# Pin_Connections.net
KiCad netlist of a schematic drawn in Altium Designer
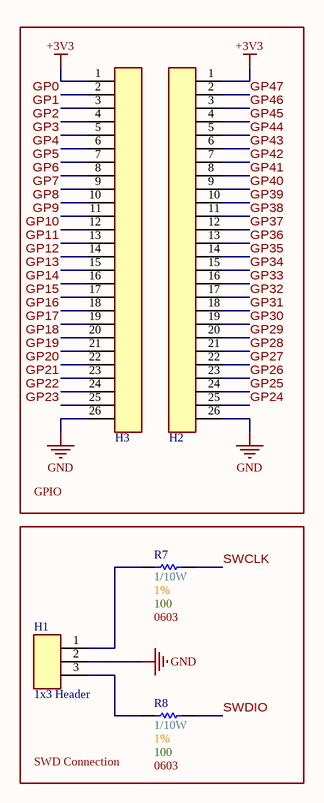
[diagram p0: Pin Connections.SchDoc]

(export (version "E")
  (design (tool "Eeschema 10.0.6"))
  (components
    (comp (ref "H1")
      (value "1x3 Header")
      (footprint "[Header] 1x3 Male")
      (description "2.54mm pitch")
      (libsource (lib "Connectors") (part "[Header] 1x3 Male"))
    )
    (comp (ref "H2")
      (value "1x26 Header")
      (footprint "[Header] 1x26 Male")
      (description "2.54mm pitch")
      (libsource (lib "") (part "[Header] 1x26 Male_1"))
    )
    (comp (ref "H3")
      (value "1x26 Header")
      (footprint "[Header] 1x26 Male")
      (description "2.54mm pitch")
      (libsource (lib "Connectors") (part "[Header] 1x26 Male"))
    )
    (comp (ref "R7")
      (value "[100] SMD 0603 1% 1/10W")
      (footprint "[Res] SMD 0603")
      (description "RC0603FR-07100RL")
      (fields
        (field (name "WATTAGE") "1/10W")
        (field (name "TOLERANCE") "1%")
        (field (name "RESISTANCE") "100")
        (field (name "SIZE PACKAGE") "0603")
      )
      (libsource (lib "Resistors") (part "[100] SMD 0603 1% 1/10W"))
    )
    (comp (ref "R8")
      (value "[100] SMD 0603 1% 1/10W")
      (footprint "[Res] SMD 0603")
      (description "RC0603FR-07100RL")
      (fields
        (field (name "WATTAGE") "1/10W")
        (field (name "TOLERANCE") "1%")
        (field (name "RESISTANCE") "100")
        (field (name "SIZE PACKAGE") "0603")
      )
      (libsource (lib "Resistors") (part "[100] SMD 0603 1% 1/10W"))
    )
  )
  (nets
    (net (code "1") (name "+3V3") (class "Default")
      (node (ref "H2") (pin "1") (pinfunction "1_1") (pintype "passive"))
      (node (ref "H3") (pin "1") (pinfunction "1_1") (pintype "passive"))
    )
    (net (code "2") (name "/GP0") (class "Default")
      (node (ref "H3") (pin "2") (pinfunction "2_2") (pintype "passive"))
    )
    (net (code "3") (name "/GP1") (class "Default")
      (node (ref "H3") (pin "3") (pinfunction "3_3") (pintype "passive"))
    )
    (net (code "4") (name "/GP2") (class "Default")
      (node (ref "H3") (pin "4") (pinfunction "4_4") (pintype "passive"))
    )
    (net (code "5") (name "/GP3") (class "Default")
      (node (ref "H3") (pin "5") (pinfunction "5_5") (pintype "passive"))
    )
    (net (code "6") (name "/GP4") (class "Default")
      (node (ref "H3") (pin "6") (pinfunction "6_6") (pintype "passive"))
    )
    (net (code "7") (name "/GP5") (class "Default")
      (node (ref "H3") (pin "7") (pinfunction "7_7") (pintype "passive"))
    )
    (net (code "8") (name "/GP6") (class "Default")
      (node (ref "H3") (pin "8") (pinfunction "8_8") (pintype "passive"))
    )
    (net (code "9") (name "/GP7") (class "Default")
      (node (ref "H3") (pin "9") (pinfunction "9_9") (pintype "passive"))
    )
    (net (code "10") (name "/GP8") (class "Default")
      (node (ref "H3") (pin "10") (pinfunction "10_10") (pintype "passive"))
    )
    (net (code "11") (name "/GP9") (class "Default")
      (node (ref "H3") (pin "11") (pinfunction "11_11") (pintype "passive"))
    )
    (net (code "12") (name "/GP10") (class "Default")
      (node (ref "H3") (pin "12") (pinfunction "12_12") (pintype "passive"))
    )
    (net (code "13") (name "/GP11") (class "Default")
      (node (ref "H3") (pin "13") (pinfunction "13_13") (pintype "passive"))
    )
    (net (code "14") (name "/GP12") (class "Default")
      (node (ref "H3") (pin "14") (pinfunction "14_14") (pintype "passive"))
    )
    (net (code "15") (name "/GP13") (class "Default")
      (node (ref "H3") (pin "15") (pinfunction "15_15") (pintype "passive"))
    )
    (net (code "16") (name "/GP14") (class "Default")
      (node (ref "H3") (pin "16") (pinfunction "16_16") (pintype "passive"))
    )
    (net (code "17") (name "/GP15") (class "Default")
      (node (ref "H3") (pin "17") (pinfunction "17_17") (pintype "passive"))
    )
    (net (code "18") (name "/GP16") (class "Default")
      (node (ref "H3") (pin "18") (pinfunction "18_18") (pintype "passive"))
    )
    (net (code "19") (name "/GP17") (class "Default")
      (node (ref "H3") (pin "19") (pinfunction "19_19") (pintype "passive"))
    )
    (net (code "20") (name "/GP18") (class "Default")
      (node (ref "H3") (pin "20") (pinfunction "20_20") (pintype "passive"))
    )
    (net (code "21") (name "/GP19") (class "Default")
      (node (ref "H3") (pin "21") (pinfunction "21_21") (pintype "passive"))
    )
    (net (code "22") (name "/GP20") (class "Default")
      (node (ref "H3") (pin "22") (pinfunction "22_22") (pintype "passive"))
    )
    (net (code "23") (name "/GP21") (class "Default")
      (node (ref "H3") (pin "23") (pinfunction "23_23") (pintype "passive"))
    )
    (net (code "24") (name "/GP22") (class "Default")
      (node (ref "H3") (pin "24") (pinfunction "24_24") (pintype "passive"))
    )
    (net (code "25") (name "/GP23") (class "Default")
      (node (ref "H3") (pin "25") (pinfunction "25_25") (pintype "passive"))
    )
    (net (code "26") (name "/GP24") (class "Default")
      (node (ref "H2") (pin "25") (pinfunction "25_25") (pintype "passive"))
    )
    (net (code "27") (name "/GP25") (class "Default")
      (node (ref "H2") (pin "24") (pinfunction "24_24") (pintype "passive"))
    )
    (net (code "28") (name "/GP26") (class "Default")
      (node (ref "H2") (pin "23") (pinfunction "23_23") (pintype "passive"))
    )
    (net (code "29") (name "/GP27") (class "Default")
      (node (ref "H2") (pin "22") (pinfunction "22_22") (pintype "passive"))
    )
    (net (code "30") (name "/GP28") (class "Default")
      (node (ref "H2") (pin "21") (pinfunction "21_21") (pintype "passive"))
    )
    (net (code "31") (name "/GP29") (class "Default")
      (node (ref "H2") (pin "20") (pinfunction "20_20") (pintype "passive"))
    )
    (net (code "32") (name "/GP30") (class "Default")
      (node (ref "H2") (pin "19") (pinfunction "19_19") (pintype "passive"))
    )
    (net (code "33") (name "/GP31") (class "Default")
      (node (ref "H2") (pin "18") (pinfunction "18_18") (pintype "passive"))
    )
    (net (code "34") (name "/GP32") (class "Default")
      (node (ref "H2") (pin "17") (pinfunction "17_17") (pintype "passive"))
    )
    (net (code "35") (name "/GP33") (class "Default")
      (node (ref "H2") (pin "16") (pinfunction "16_16") (pintype "passive"))
    )
    (net (code "36") (name "/GP34") (class "Default")
      (node (ref "H2") (pin "15") (pinfunction "15_15") (pintype "passive"))
    )
    (net (code "37") (name "/GP35") (class "Default")
      (node (ref "H2") (pin "14") (pinfunction "14_14") (pintype "passive"))
    )
    (net (code "38") (name "/GP36") (class "Default")
      (node (ref "H2") (pin "13") (pinfunction "13_13") (pintype "passive"))
    )
    (net (code "39") (name "/GP37") (class "Default")
      (node (ref "H2") (pin "12") (pinfunction "12_12") (pintype "passive"))
    )
    (net (code "40") (name "/GP38") (class "Default")
      (node (ref "H2") (pin "11") (pinfunction "11_11") (pintype "passive"))
    )
    (net (code "41") (name "/GP39") (class "Default")
      (node (ref "H2") (pin "10") (pinfunction "10_10") (pintype "passive"))
    )
    (net (code "42") (name "/GP40") (class "Default")
      (node (ref "H2") (pin "9") (pinfunction "9_9") (pintype "passive"))
    )
    (net (code "43") (name "/GP41") (class "Default")
      (node (ref "H2") (pin "8") (pinfunction "8_8") (pintype "passive"))
    )
    (net (code "44") (name "/GP42") (class "Default")
      (node (ref "H2") (pin "7") (pinfunction "7_7") (pintype "passive"))
    )
    (net (code "45") (name "/GP43") (class "Default")
      (node (ref "H2") (pin "6") (pinfunction "6_6") (pintype "passive"))
    )
    (net (code "46") (name "/GP44") (class "Default")
      (node (ref "H2") (pin "5") (pinfunction "5_5") (pintype "passive"))
    )
    (net (code "47") (name "/GP45") (class "Default")
      (node (ref "H2") (pin "4") (pinfunction "4_4") (pintype "passive"))
    )
    (net (code "48") (name "/GP46") (class "Default")
      (node (ref "H2") (pin "3") (pinfunction "3_3") (pintype "passive"))
    )
    (net (code "49") (name "/GP47") (class "Default")
      (node (ref "H2") (pin "2") (pinfunction "2_2") (pintype "passive"))
    )
    (net (code "50") (name "/SWCLK") (class "Default")
      (node (ref "R7") (pin "2") (pinfunction "2_2") (pintype "passive"))
    )
    (net (code "51") (name "/SWDIO") (class "Default")
      (node (ref "R8") (pin "2") (pinfunction "2_2") (pintype "passive"))
    )
    (net (code "52") (name "GND") (class "Default")
      (node (ref "H1") (pin "2") (pintype "passive"))
      (node (ref "H2") (pin "26") (pinfunction "26_26") (pintype "passive"))
      (node (ref "H3") (pin "26") (pinfunction "26_26") (pintype "passive"))
    )
    (net (code "53") (name "Net-(H1-Pad1)") (class "Default")
      (node (ref "H1") (pin "1") (pintype "passive"))
      (node (ref "R7") (pin "1") (pinfunction "1_1") (pintype "passive"))
    )
    (net (code "54") (name "Net-(H1-Pad3)") (class "Default")
      (node (ref "H1") (pin "3") (pintype "passive"))
      (node (ref "R8") (pin "1") (pinfunction "1_1") (pintype "passive"))
    )
  )
)
